# PORTS.net
KiCad netlist of a schematic drawn in Altium Designer
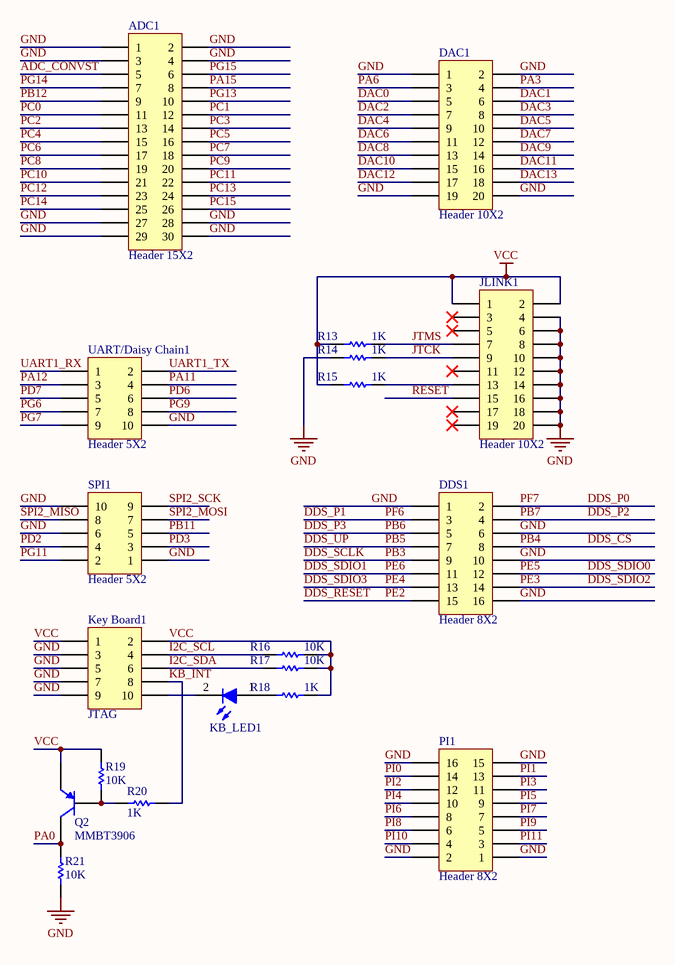
[diagram p0: PORTS.SchDoc]

(export (version "E")
  (design (tool "Eeschema 10.0.6"))
  (components
    (comp (ref "ADC1")
      (value "Header 15X2")
      (footprint "HEADER15X2")
      (description "Header, 15-Pin, Dual row")
      (fields (field (name "PUBLISHER") "Altium Limited"))
      (libsource (lib "Miscellaneous Connectors") (part "Header 15X2"))
    )
    (comp (ref "DAC1")
      (value "Header 10X2")
      (footprint "HEADER10X2")
      (description "Header, 10-Pin, Dual row")
      (fields (field (name "PUBLISHER") "Altium Limited"))
      (libsource (lib "Miscellaneous Connectors") (part "Header 10X2"))
    )
    (comp (ref "DDS1")
      (value "Header 8X2")
      (footprint "Header8X2")
      (description "Header, 8-Pin, Dual row")
      (fields (field (name "PUBLISHER") "Altium Limited"))
      (libsource (lib "") (part "Header 8X2_1"))
    )
    (comp (ref "JLINK1")
      (value "Header 10X2")
      (footprint "HEADER10X2")
      (description "Header, 10-Pin, Dual row")
      (fields (field (name "PUBLISHER") "Altium Limited"))
      (libsource (lib "Miscellaneous Connectors") (part "Header 10X2"))
    )
    (comp (ref "KB_LED1")
      (value "LED-BLUE")
      (footprint "0603LED_BLUE_V")
      (libsource (lib "Slivy's ibrary") (part "LED-BLUE"))
    )
    (comp (ref "Key Board1")
      (value "JTAG")
      (footprint "HEADER5X2")
      (description "Header, 5-Pin, Dual row")
      (fields (field (name "MANUFACTURER") "Generic Components"))
      (libsource (lib "Integrated_Library1") (part "Header 5X2"))
    )
    (comp (ref "PI1")
      (value "Header 8X2")
      (footprint "HEADER8X2")
      (description "Header, 8-Pin, Dual row")
      (fields (field (name "PUBLISHER") "Altium Limited"))
      (libsource (lib "Miscellaneous Connectors") (part "Header 8X2"))
    )
    (comp (ref "Q2")
      (value "MMBT3906")
      (footprint "SOT23_M")
      (description "PNP General Purpose Amplifier")
      (fields (field (name "PUBLISHER") "Altium Limited"))
      (libsource (lib "Slivy's ibrary") (part "MMBT3906"))
    )
    (comp (ref "R13")
      (value "1K")
      (footprint "RESC0603(1608)_M")
      (libsource (lib "Slivy's Library") (part "RES"))
    )
    (comp (ref "R14")
      (value "1K")
      (footprint "RESC0603(1608)_M")
      (libsource (lib "Slivy's Library") (part "RES"))
    )
    (comp (ref "R15")
      (value "1K")
      (footprint "RESC0603(1608)_M")
      (libsource (lib "Slivy's Library") (part "RES"))
    )
    (comp (ref "R16")
      (value "10K")
      (footprint "RESC0603(1608)_M")
      (libsource (lib "Slivy's Library") (part "RES"))
    )
    (comp (ref "R17")
      (value "10K")
      (footprint "RESC0603(1608)_M")
      (libsource (lib "Slivy's Library") (part "RES"))
    )
    (comp (ref "R18")
      (value "1K")
      (footprint "RESC0603(1608)_M")
      (libsource (lib "Slivy's Library") (part "RES"))
    )
    (comp (ref "R19")
      (value "10K")
      (footprint "RESC0603(1608)_M")
      (libsource (lib "Slivy's ibrary") (part "RES"))
    )
    (comp (ref "R20")
      (value "1K")
      (footprint "RESC0603(1608)_M")
      (libsource (lib "Slivy's ibrary") (part "RES"))
    )
    (comp (ref "R21")
      (value "10K")
      (footprint "RESC0603(1608)_M")
      (libsource (lib "Slivy's ibrary") (part "RES"))
    )
    (comp (ref "SPI1")
      (value "Header 5X2")
      (footprint "HEADER5X2")
      (description "Header, 5-Pin, Dual row")
      (fields (field (name "PUBLISHER") "Altium Limited"))
      (libsource (lib "") (part "Header 5X2_1"))
    )
    (comp (ref "UART/Daisy Chain1")
      (value "Header 5X2")
      (footprint "HEADER5X2")
      (description "Header, 5-Pin, Dual row")
      (fields (field (name "PUBLISHER") "Altium Limited"))
      (libsource (lib "Miscellaneous Connectors") (part "Header 5X2"))
    )
  )
  (nets
    (net (code "1") (name "/ADC_CONVST") (class "Default")
      (node (ref "ADC1") (pin "5") (pinfunction "5_5") (pintype "passive"))
    )
    (net (code "2") (name "/DAC0") (class "Default")
      (node (ref "DAC1") (pin "5") (pinfunction "5_5") (pintype "passive"))
    )
    (net (code "3") (name "/DAC1") (class "Default")
      (node (ref "DAC1") (pin "6") (pinfunction "6_6") (pintype "passive"))
    )
    (net (code "4") (name "/DAC2") (class "Default")
      (node (ref "DAC1") (pin "7") (pinfunction "7_7") (pintype "passive"))
    )
    (net (code "5") (name "/DAC3") (class "Default")
      (node (ref "DAC1") (pin "8") (pinfunction "8_8") (pintype "passive"))
    )
    (net (code "6") (name "/DAC4") (class "Default")
      (node (ref "DAC1") (pin "9") (pinfunction "9_9") (pintype "passive"))
    )
    (net (code "7") (name "/DAC5") (class "Default")
      (node (ref "DAC1") (pin "10") (pinfunction "10_10") (pintype "passive"))
    )
    (net (code "8") (name "/DAC6") (class "Default")
      (node (ref "DAC1") (pin "11") (pinfunction "11_11") (pintype "passive"))
    )
    (net (code "9") (name "/DAC7") (class "Default")
      (node (ref "DAC1") (pin "12") (pinfunction "12_12") (pintype "passive"))
    )
    (net (code "10") (name "/DAC8") (class "Default")
      (node (ref "DAC1") (pin "13") (pinfunction "13_13") (pintype "passive"))
    )
    (net (code "11") (name "/DAC9") (class "Default")
      (node (ref "DAC1") (pin "14") (pinfunction "14_14") (pintype "passive"))
    )
    (net (code "12") (name "/DAC10") (class "Default")
      (node (ref "DAC1") (pin "15") (pinfunction "15_15") (pintype "passive"))
    )
    (net (code "13") (name "/DAC11") (class "Default")
      (node (ref "DAC1") (pin "16") (pinfunction "16_16") (pintype "passive"))
    )
    (net (code "14") (name "/DAC12") (class "Default")
      (node (ref "DAC1") (pin "17") (pinfunction "17_17") (pintype "passive"))
    )
    (net (code "15") (name "/DAC13") (class "Default")
      (node (ref "DAC1") (pin "18") (pinfunction "18_18") (pintype "passive"))
    )
    (net (code "16") (name "/DDS_CS") (class "Default")
      (node (ref "DDS1") (pin "8") (pinfunction "8_8") (pintype "passive"))
    )
    (net (code "17") (name "/DDS_P0") (class "Default")
      (node (ref "DDS1") (pin "2") (pinfunction "2_2") (pintype "passive"))
    )
    (net (code "18") (name "/DDS_P1") (class "Default")
      (node (ref "DDS1") (pin "3") (pinfunction "3_3") (pintype "passive"))
    )
    (net (code "19") (name "/DDS_P2") (class "Default")
      (node (ref "DDS1") (pin "4") (pinfunction "4_4") (pintype "passive"))
    )
    (net (code "20") (name "/DDS_P3") (class "Default")
      (node (ref "DDS1") (pin "5") (pinfunction "5_5") (pintype "passive"))
    )
    (net (code "21") (name "/DDS_RESET") (class "Default")
      (node (ref "DDS1") (pin "15") (pinfunction "15_15") (pintype "passive"))
    )
    (net (code "22") (name "/DDS_SCLK") (class "Default")
      (node (ref "DDS1") (pin "9") (pinfunction "9_9") (pintype "passive"))
    )
    (net (code "23") (name "/DDS_SDIO0") (class "Default")
      (node (ref "DDS1") (pin "12") (pinfunction "12_12") (pintype "passive"))
    )
    (net (code "24") (name "/DDS_SDIO1") (class "Default")
      (node (ref "DDS1") (pin "11") (pinfunction "11_11") (pintype "passive"))
    )
    (net (code "25") (name "/DDS_SDIO2") (class "Default")
      (node (ref "DDS1") (pin "14") (pinfunction "14_14") (pintype "passive"))
    )
    (net (code "26") (name "/DDS_SDIO3") (class "Default")
      (node (ref "DDS1") (pin "13") (pinfunction "13_13") (pintype "passive"))
    )
    (net (code "27") (name "/DDS_UP") (class "Default")
      (node (ref "DDS1") (pin "7") (pinfunction "7_7") (pintype "passive"))
    )
    (net (code "28") (name "/I2C_SCL") (class "Default")
      (node (ref "Key Board1") (pin "4") (pinfunction "4_4") (pintype "passive"))
      (node (ref "R16") (pin "2") (pinfunction "2_2") (pintype "passive"))
    )
    (net (code "29") (name "/I2C_SDA") (class "Default")
      (node (ref "Key Board1") (pin "6") (pinfunction "6_6") (pintype "passive"))
      (node (ref "R17") (pin "2") (pinfunction "2_2") (pintype "passive"))
    )
    (net (code "30") (name "/JTCK") (class "Default")
      (node (ref "JLINK1") (pin "9") (pinfunction "9_9") (pintype "passive"))
      (node (ref "R14") (pin "1") (pinfunction "1_1") (pintype "passive"))
    )
    (net (code "31") (name "/JTMS") (class "Default")
      (node (ref "JLINK1") (pin "7") (pinfunction "7_7") (pintype "passive"))
      (node (ref "R13") (pin "1") (pinfunction "1_1") (pintype "passive"))
    )
    (net (code "32") (name "/KB_INT") (class "Default")
      (node (ref "Key Board1") (pin "8") (pinfunction "8_8") (pintype "passive"))
      (node (ref "R20") (pin "2") (pinfunction "2_2") (pintype "passive"))
    )
    (net (code "33") (name "/PA0") (class "Default")
      (node (ref "Q2") (pin "3") (pinfunction "C_3") (pintype "passive"))
      (node (ref "R21") (pin "2") (pinfunction "2_2") (pintype "passive"))
    )
    (net (code "34") (name "/PA3") (class "Default")
      (node (ref "DAC1") (pin "4") (pinfunction "4_4") (pintype "passive"))
    )
    (net (code "35") (name "/PA6") (class "Default")
      (node (ref "DAC1") (pin "3") (pinfunction "3_3") (pintype "passive"))
    )
    (net (code "36") (name "/PA11") (class "Default")
      (node (ref "UART/Daisy Chain1") (pin "4") (pinfunction "4_4") (pintype "passive"))
    )
    (net (code "37") (name "/PA12") (class "Default")
      (node (ref "UART/Daisy Chain1") (pin "3") (pinfunction "3_3") (pintype "passive"))
    )
    (net (code "38") (name "/PA15") (class "Default")
      (node (ref "ADC1") (pin "8") (pinfunction "8_8") (pintype "passive"))
    )
    (net (code "39") (name "/PB11") (class "Default")
      (node (ref "SPI1") (pin "5") (pinfunction "5_5") (pintype "passive"))
    )
    (net (code "40") (name "/PB12") (class "Default")
      (node (ref "ADC1") (pin "9") (pinfunction "9_9") (pintype "passive"))
    )
    (net (code "41") (name "/PC0") (class "Default")
      (node (ref "ADC1") (pin "11") (pinfunction "11_11") (pintype "passive"))
    )
    (net (code "42") (name "/PC1") (class "Default")
      (node (ref "ADC1") (pin "12") (pinfunction "12_12") (pintype "passive"))
    )
    (net (code "43") (name "/PC2") (class "Default")
      (node (ref "ADC1") (pin "13") (pinfunction "13_13") (pintype "passive"))
    )
    (net (code "44") (name "/PC3") (class "Default")
      (node (ref "ADC1") (pin "14") (pinfunction "14_14") (pintype "passive"))
    )
    (net (code "45") (name "/PC4") (class "Default")
      (node (ref "ADC1") (pin "15") (pinfunction "15_15") (pintype "passive"))
    )
    (net (code "46") (name "/PC5") (class "Default")
      (node (ref "ADC1") (pin "16") (pinfunction "16_16") (pintype "passive"))
    )
    (net (code "47") (name "/PC6") (class "Default")
      (node (ref "ADC1") (pin "17") (pinfunction "17_17") (pintype "passive"))
    )
    (net (code "48") (name "/PC7") (class "Default")
      (node (ref "ADC1") (pin "18") (pinfunction "18_18") (pintype "passive"))
    )
    (net (code "49") (name "/PC8") (class "Default")
      (node (ref "ADC1") (pin "19") (pinfunction "19_19") (pintype "passive"))
    )
    (net (code "50") (name "/PC9") (class "Default")
      (node (ref "ADC1") (pin "20") (pinfunction "20_20") (pintype "passive"))
    )
    (net (code "51") (name "/PC10") (class "Default")
      (node (ref "ADC1") (pin "21") (pinfunction "21_21") (pintype "passive"))
    )
    (net (code "52") (name "/PC11") (class "Default")
      (node (ref "ADC1") (pin "22") (pinfunction "22_22") (pintype "passive"))
    )
    (net (code "53") (name "/PC12") (class "Default")
      (node (ref "ADC1") (pin "23") (pinfunction "23_23") (pintype "passive"))
    )
    (net (code "54") (name "/PC13") (class "Default")
      (node (ref "ADC1") (pin "24") (pinfunction "24_24") (pintype "passive"))
    )
    (net (code "55") (name "/PC14") (class "Default")
      (node (ref "ADC1") (pin "25") (pinfunction "25_25") (pintype "passive"))
    )
    (net (code "56") (name "/PC15") (class "Default")
      (node (ref "ADC1") (pin "26") (pinfunction "26_26") (pintype "passive"))
    )
    (net (code "57") (name "/PD2") (class "Default")
      (node (ref "SPI1") (pin "4") (pinfunction "4_4") (pintype "passive"))
    )
    (net (code "58") (name "/PD3") (class "Default")
      (node (ref "SPI1") (pin "3") (pinfunction "3_3") (pintype "passive"))
    )
    (net (code "59") (name "/PD6") (class "Default")
      (node (ref "UART/Daisy Chain1") (pin "6") (pinfunction "6_6") (pintype "passive"))
    )
    (net (code "60") (name "/PD7") (class "Default")
      (node (ref "UART/Daisy Chain1") (pin "5") (pinfunction "5_5") (pintype "passive"))
    )
    (net (code "61") (name "/PG6") (class "Default")
      (node (ref "UART/Daisy Chain1") (pin "7") (pinfunction "7_7") (pintype "passive"))
    )
    (net (code "62") (name "/PG7") (class "Default")
      (node (ref "UART/Daisy Chain1") (pin "9") (pinfunction "9_9") (pintype "passive"))
    )
    (net (code "63") (name "/PG9") (class "Default")
      (node (ref "UART/Daisy Chain1") (pin "8") (pinfunction "8_8") (pintype "passive"))
    )
    (net (code "64") (name "/PG11") (class "Default")
      (node (ref "SPI1") (pin "2") (pinfunction "2_2") (pintype "passive"))
    )
    (net (code "65") (name "/PG13") (class "Default")
      (node (ref "ADC1") (pin "10") (pinfunction "10_10") (pintype "passive"))
    )
    (net (code "66") (name "/PG14") (class "Default")
      (node (ref "ADC1") (pin "7") (pinfunction "7_7") (pintype "passive"))
    )
    (net (code "67") (name "/PG15") (class "Default")
      (node (ref "ADC1") (pin "6") (pinfunction "6_6") (pintype "passive"))
    )
    (net (code "68") (name "/PI0") (class "Default")
      (node (ref "PI1") (pin "14") (pinfunction "14_14") (pintype "passive"))
    )
    (net (code "69") (name "/PI1") (class "Default")
      (node (ref "PI1") (pin "13") (pinfunction "13_13") (pintype "passive"))
    )
    (net (code "70") (name "/PI2") (class "Default")
      (node (ref "PI1") (pin "12") (pinfunction "12_12") (pintype "passive"))
    )
    (net (code "71") (name "/PI3") (class "Default")
      (node (ref "PI1") (pin "11") (pinfunction "11_11") (pintype "passive"))
    )
    (net (code "72") (name "/PI4") (class "Default")
      (node (ref "PI1") (pin "10") (pinfunction "10_10") (pintype "passive"))
    )
    (net (code "73") (name "/PI5") (class "Default")
      (node (ref "PI1") (pin "9") (pinfunction "9_9") (pintype "passive"))
    )
    (net (code "74") (name "/PI6") (class "Default")
      (node (ref "PI1") (pin "8") (pinfunction "8_8") (pintype "passive"))
    )
    (net (code "75") (name "/PI7") (class "Default")
      (node (ref "PI1") (pin "7") (pinfunction "7_7") (pintype "passive"))
    )
    (net (code "76") (name "/PI8") (class "Default")
      (node (ref "PI1") (pin "6") (pinfunction "6_6") (pintype "passive"))
    )
    (net (code "77") (name "/PI9") (class "Default")
      (node (ref "PI1") (pin "5") (pinfunction "5_5") (pintype "passive"))
    )
    (net (code "78") (name "/PI10") (class "Default")
      (node (ref "PI1") (pin "4") (pinfunction "4_4") (pintype "passive"))
    )
    (net (code "79") (name "/PI11") (class "Default")
      (node (ref "PI1") (pin "3") (pinfunction "3_3") (pintype "passive"))
    )
    (net (code "80") (name "/RESET") (class "Default")
      (node (ref "JLINK1") (pin "15") (pinfunction "15_15") (pintype "passive"))
    )
    (net (code "81") (name "/SPI2_MISO") (class "Default")
      (node (ref "SPI1") (pin "8") (pinfunction "8_8") (pintype "passive"))
    )
    (net (code "82") (name "/SPI2_MOSI") (class "Default")
      (node (ref "SPI1") (pin "7") (pinfunction "7_7") (pintype "passive"))
    )
    (net (code "83") (name "/SPI2_SCK") (class "Default")
      (node (ref "SPI1") (pin "9") (pinfunction "9_9") (pintype "passive"))
    )
    (net (code "84") (name "/UART1_RX") (class "Default")
      (node (ref "UART/Daisy Chain1") (pin "1") (pinfunction "1_1") (pintype "passive"))
    )
    (net (code "85") (name "/UART1_TX") (class "Default")
      (node (ref "UART/Daisy Chain1") (pin "2") (pinfunction "2_2") (pintype "passive"))
    )
    (net (code "86") (name "GND") (class "Default")
      (node (ref "ADC1") (pin "1") (pinfunction "1_1") (pintype "passive"))
      (node (ref "ADC1") (pin "2") (pinfunction "2_2") (pintype "passive"))
      (node (ref "ADC1") (pin "27") (pinfunction "27_27") (pintype "passive"))
      (node (ref "ADC1") (pin "28") (pinfunction "28_28") (pintype "passive"))
      (node (ref "ADC1") (pin "29") (pinfunction "29_29") (pintype "passive"))
      (node (ref "ADC1") (pin "3") (pinfunction "3_3") (pintype "passive"))
      (node (ref "ADC1") (pin "30") (pinfunction "30_30") (pintype "passive"))
      (node (ref "ADC1") (pin "4") (pinfunction "4_4") (pintype "passive"))
      (node (ref "DAC1") (pin "1") (pinfunction "1_1") (pintype "passive"))
      (node (ref "DAC1") (pin "19") (pinfunction "19_19") (pintype "passive"))
      (node (ref "DAC1") (pin "2") (pinfunction "2_2") (pintype "passive"))
      (node (ref "DAC1") (pin "20") (pinfunction "20_20") (pintype "passive"))
      (node (ref "DDS1") (pin "1") (pinfunction "1_1") (pintype "passive"))
      (node (ref "DDS1") (pin "10") (pinfunction "10_10") (pintype "passive"))
      (node (ref "DDS1") (pin "16") (pinfunction "16_16") (pintype "passive"))
      (node (ref "DDS1") (pin "6") (pinfunction "6_6") (pintype "passive"))
      (node (ref "JLINK1") (pin "10") (pinfunction "10_10") (pintype "passive"))
      (node (ref "JLINK1") (pin "12") (pinfunction "12_12") (pintype "passive"))
      (node (ref "JLINK1") (pin "14") (pinfunction "14_14") (pintype "passive"))
      (node (ref "JLINK1") (pin "16") (pinfunction "16_16") (pintype "passive"))
      (node (ref "JLINK1") (pin "18") (pinfunction "18_18") (pintype "passive"))
      (node (ref "JLINK1") (pin "20") (pinfunction "20_20") (pintype "passive"))
      (node (ref "JLINK1") (pin "4") (pinfunction "4_4") (pintype "passive"))
      (node (ref "JLINK1") (pin "6") (pinfunction "6_6") (pintype "passive"))
      (node (ref "JLINK1") (pin "8") (pinfunction "8_8") (pintype "passive"))
      (node (ref "Key Board1") (pin "3") (pinfunction "3_3") (pintype "passive"))
      (node (ref "Key Board1") (pin "5") (pinfunction "5_5") (pintype "passive"))
      (node (ref "Key Board1") (pin "7") (pinfunction "7_7") (pintype "passive"))
      (node (ref "Key Board1") (pin "9") (pinfunction "9_9") (pintype "passive"))
      (node (ref "PI1") (pin "1") (pinfunction "1_1") (pintype "passive"))
      (node (ref "PI1") (pin "15") (pinfunction "15_15") (pintype "passive"))
      (node (ref "PI1") (pin "16") (pinfunction "16_16") (pintype "passive"))
      (node (ref "PI1") (pin "2") (pinfunction "2_2") (pintype "passive"))
      (node (ref "R14") (pin "2") (pinfunction "2_2") (pintype "passive"))
      (node (ref "R21") (pin "1") (pinfunction "1_1") (pintype "passive"))
      (node (ref "SPI1") (pin "1") (pinfunction "1_1") (pintype "passive"))
      (node (ref "SPI1") (pin "10") (pinfunction "10_10") (pintype "passive"))
      (node (ref "SPI1") (pin "6") (pinfunction "6_6") (pintype "passive"))
      (node (ref "UART/Daisy Chain1") (pin "10") (pinfunction "10_10") (pintype "passive"))
    )
    (net (code "87") (name "Net-(JLINK1-Pad13)") (class "Default")
      (node (ref "JLINK1") (pin "13") (pinfunction "13_13") (pintype "passive"))
      (node (ref "R15") (pin "1") (pinfunction "1_1") (pintype "passive"))
    )
    (net (code "88") (name "Net-(KB_LED1-A)") (class "Default")
      (node (ref "KB_LED1") (pin "1") (pinfunction "A_1") (pintype "passive"))
      (node (ref "R18") (pin "2") (pinfunction "2_2") (pintype "passive"))
    )
    (net (code "89") (name "Net-(KB_LED1-K)") (class "Default")
      (node (ref "KB_LED1") (pin "2") (pinfunction "K_2") (pintype "passive"))
      (node (ref "Key Board1") (pin "10") (pinfunction "10_10") (pintype "passive"))
    )
    (net (code "90") (name "Net-(Q2-B)") (class "Default")
      (node (ref "Q2") (pin "1") (pinfunction "B_1") (pintype "passive"))
      (node (ref "R19") (pin "1") (pinfunction "1_1") (pintype "passive"))
      (node (ref "R20") (pin "1") (pinfunction "1_1") (pintype "passive"))
    )
    (net (code "91") (name "VCC") (class "Default")
      (node (ref "JLINK1") (pin "1") (pinfunction "1_1") (pintype "passive"))
      (node (ref "JLINK1") (pin "2") (pinfunction "2_2") (pintype "passive"))
      (node (ref "Key Board1") (pin "1") (pinfunction "1_1") (pintype "passive"))
      (node (ref "Key Board1") (pin "2") (pinfunction "2_2") (pintype "passive"))
      (node (ref "Q2") (pin "2") (pinfunction "E_2") (pintype "passive"))
      (node (ref "R13") (pin "2") (pinfunction "2_2") (pintype "passive"))
      (node (ref "R15") (pin "2") (pinfunction "2_2") (pintype "passive"))
      (node (ref "R16") (pin "1") (pinfunction "1_1") (pintype "passive"))
      (node (ref "R17") (pin "1") (pinfunction "1_1") (pintype "passive"))
      (node (ref "R18") (pin "1") (pinfunction "1_1") (pintype "passive"))
      (node (ref "R19") (pin "2") (pinfunction "2_2") (pintype "passive"))
    )
    (net (code "92") (name "unconnected-(JLINK1-Pad3)") (class "Default")
      (node (ref "JLINK1") (pin "3") (pinfunction "3_3") (pintype "passive+no_connect"))
    )
    (net (code "93") (name "unconnected-(JLINK1-Pad5)") (class "Default")
      (node (ref "JLINK1") (pin "5") (pinfunction "5_5") (pintype "passive+no_connect"))
    )
    (net (code "94") (name "unconnected-(JLINK1-Pad11)") (class "Default")
      (node (ref "JLINK1") (pin "11") (pinfunction "11_11") (pintype "passive+no_connect"))
    )
    (net (code "95") (name "unconnected-(JLINK1-Pad17)") (class "Default")
      (node (ref "JLINK1") (pin "17") (pinfunction "17_17") (pintype "passive+no_connect"))
    )
    (net (code "96") (name "unconnected-(JLINK1-Pad19)") (class "Default")
      (node (ref "JLINK1") (pin "19") (pinfunction "19_19") (pintype "passive+no_connect"))
    )
  )
)
